# MDL_CONTROL.net
KiCad netlist of a schematic drawn in Altium Designer
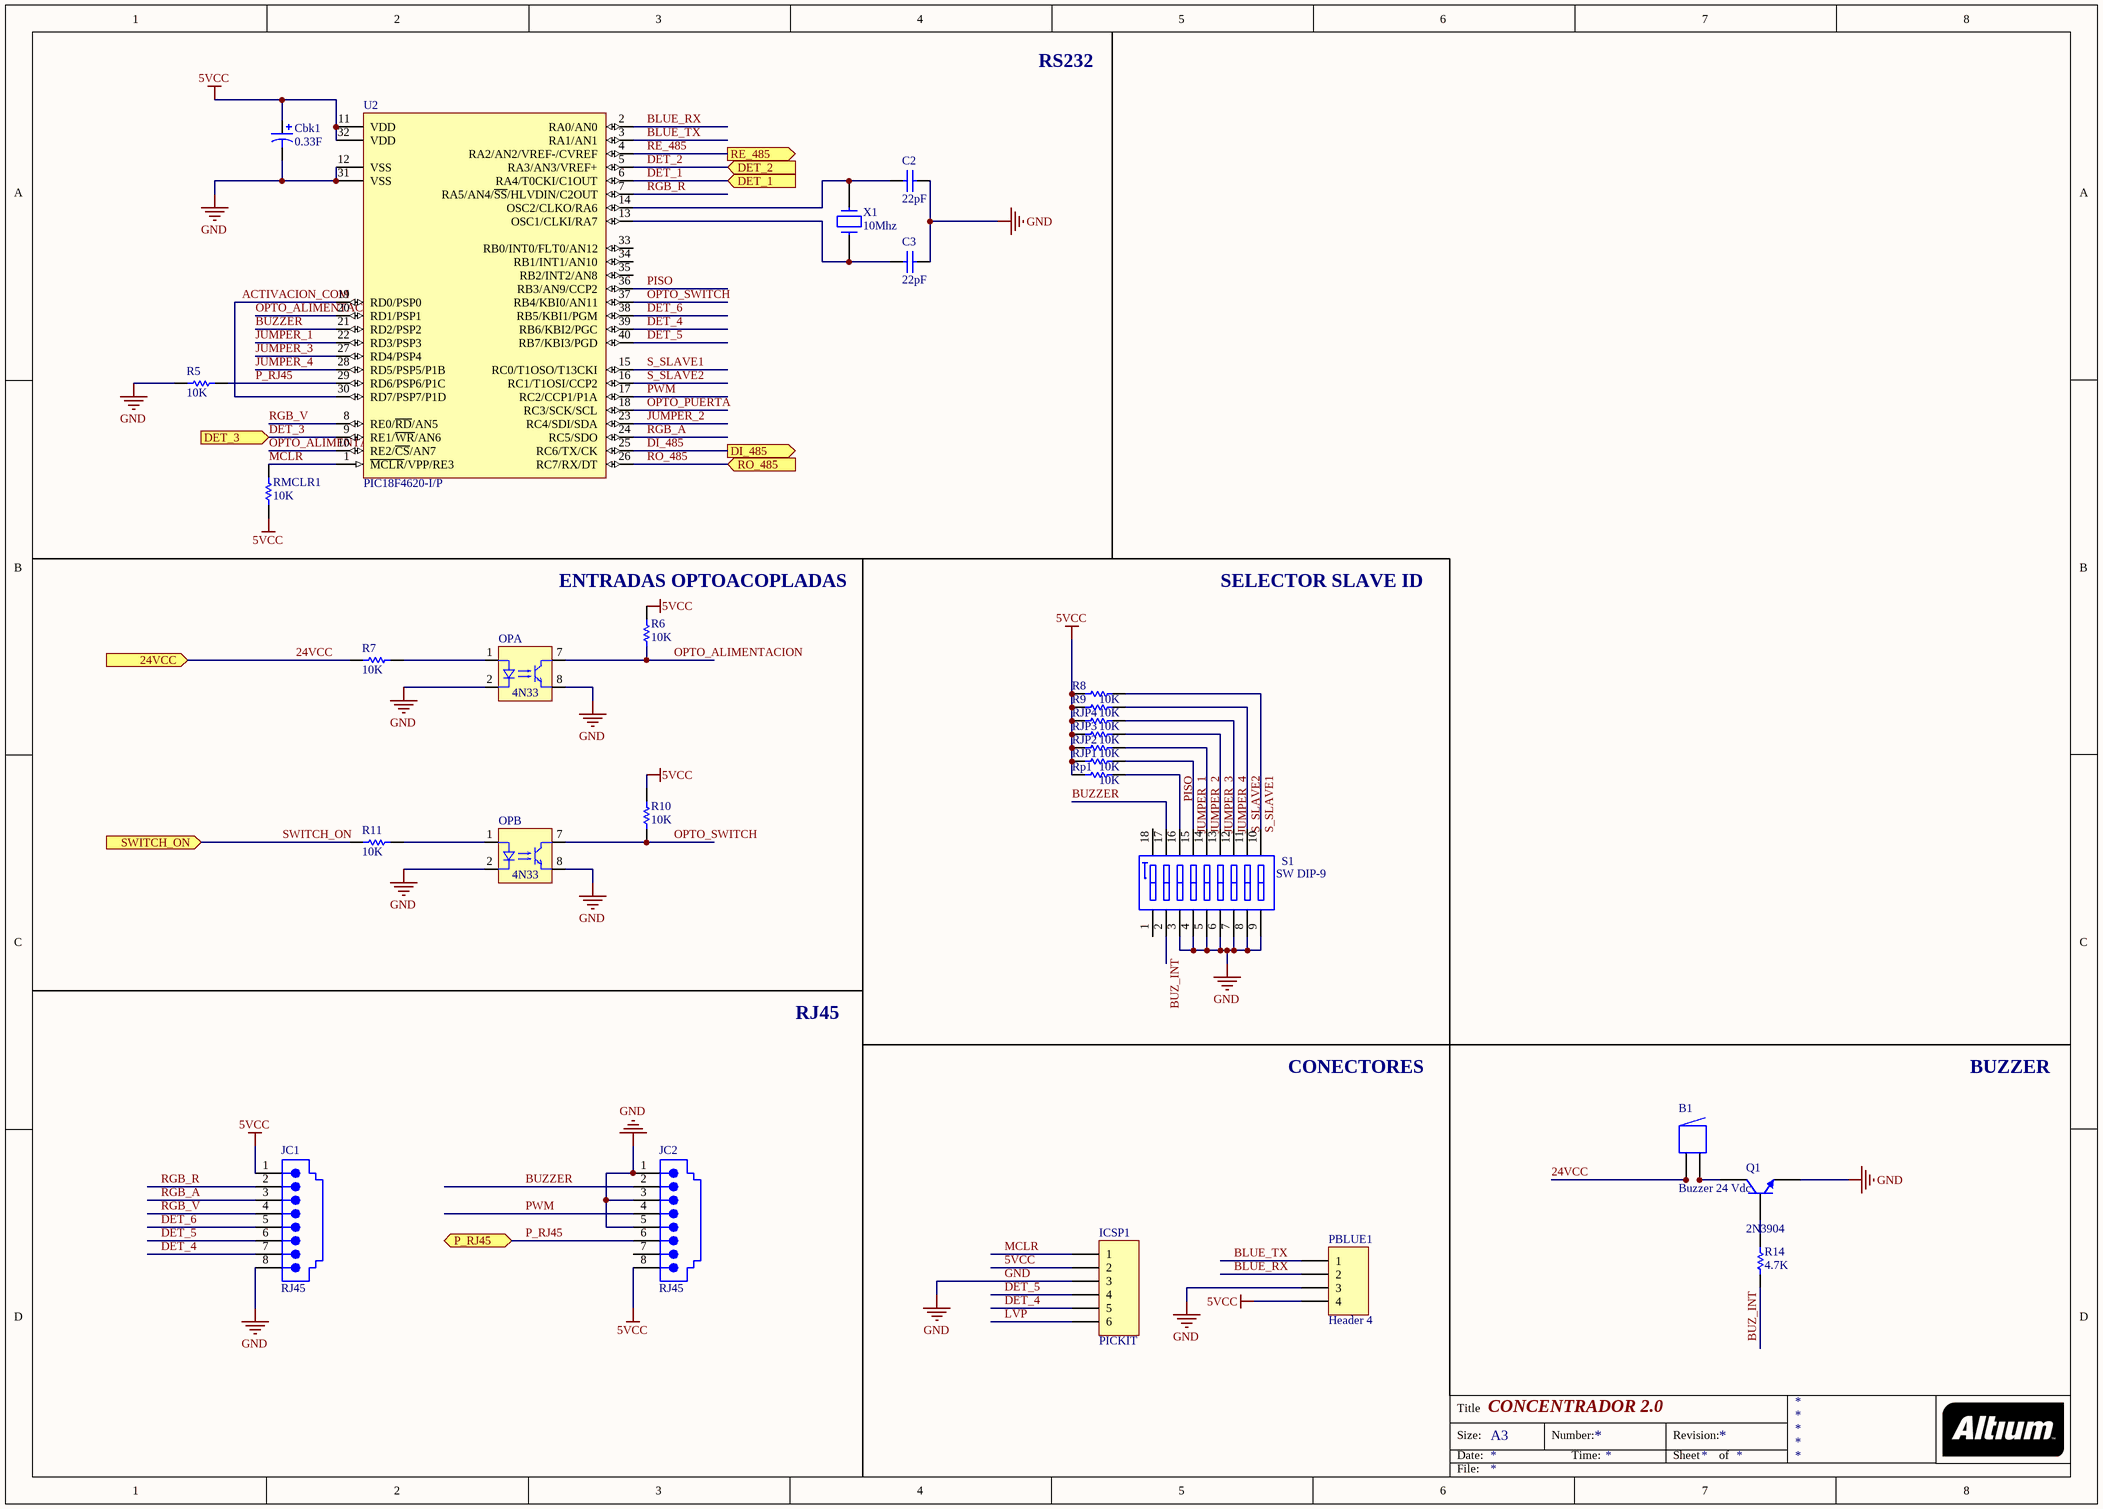
[diagram p0: MDL_CONTROL.SchDoc]

(export (version "E")
  (design (tool "Eeschema 10.0.6"))
  (components
    (comp (ref "B1")
      (value "Buzzer 24 Vdc")
      (footprint "ABSM-1574")
      (description "Magnetic Transducer Buzzer")
      (fields (field (name "PUBLISHER") "Altium Limited"))
      (libsource (lib "Miscellaneous Devices") (part "Buzzer"))
    )
    (comp (ref "C2")
      (value "22pF")
      (footprint "VP31-2.5")
      (description "Dipped Radial Multilayer Ceramic Capacitor COG (NPO): 22pF, 100V")
      (fields (field (name "Comment") "VP31BA220JB") (field (name "PUBLISHER") "Altium Limited"))
      (libsource (lib "Vishay Vitramon Ceramic Dipped Capacitor") (part "VP31BA220JB"))
    )
    (comp (ref "C3")
      (value "22pF")
      (footprint "VP31-2.5")
      (description "Dipped Radial Multilayer Ceramic Capacitor COG (NPO): 22pF, 100V")
      (fields (field (name "Comment") "VP31BA220JB") (field (name "PUBLISHER") "Altium Limited"))
      (libsource (lib "Vishay Vitramon Ceramic Dipped Capacitor") (part "VP31BA220JB"))
    )
    (comp (ref "Cbk1")
      (value "0.33F")
      (footprint "C1000UF")
      (description "Polarized Capacitor (Radial)")
      (fields (field (name "Comment") "Cap Pol1") (field (name "PUBLISHER") "Altium Limited"))
      (libsource (lib "CONTROL BARRAS DE CONTEO") (part "Cap Pol1"))
    )
    (comp (ref "ICSP1")
      (value "PICKIT")
      (footprint "HDR1X6")
      (description "Header, 6-Pin")
      (fields (field (name "PUBLISHER") "Altium Limited"))
      (libsource (lib "CONTROL BARRAS DE CONTEO") (part "Header 6"))
    )
    (comp (ref "JC1")
      (value "RJ45")
      (footprint "15-43-6233")
      (description "Right Angle, Standard Profile, RJ45-Keyed, Flange Mount PCB Jack")
      (fields (field (name "PUBLISHER") "Altium Limited"))
      (libsource (lib "Molex Modular Jack Right Angle") (part "15-43-6233"))
    )
    (comp (ref "JC2")
      (value "RJ45")
      (footprint "15-43-6233")
      (description "Right Angle, Standard Profile, RJ45-Keyed, Flange Mount PCB Jack")
      (fields (field (name "PUBLISHER") "Altium Limited"))
      (libsource (lib "Molex Modular Jack Right Angle") (part "15-43-6233"))
    )
    (comp (ref "OP")
      (value "4N33")
      (footprint "4n35_4n33_6pines")
      (description "Optocoupler, Phototransistor Output, Dual Channel, TTL Compatible, Pb-free")
      (fields (field (name "PUBLISHER") "Altium Limited"))
      (libsource (lib "Vishay Optoelectronic Optocoupler") (part "ILD74"))
    )
    (comp (ref "PBLUE1")
      (value "Header 4")
      (footprint "HDR1X4")
      (description "Header, 4-Pin")
      (fields (field (name "PUBLISHER") "Altium Limited"))
      (libsource (lib "Miscellaneous Connectors") (part "Header 4"))
    )
    (comp (ref "Q1")
      (value "2N3904")
      (footprint "TO-92A")
      (description "NPN General Purpose Amplifier")
      (fields (field (name "PUBLISHER") "Altium Limited"))
      (libsource (lib "Miscellaneous Devices") (part "2N3904"))
    )
    (comp (ref "R5")
      (value "10K")
      (footprint "AXIAL-0.3")
      (description "Resistor")
      (fields (field (name "Comment") "Res") (field (name "PUBLISHER") "Altium Limited"))
      (libsource (lib "Miscellaneous Devices") (part "Res1"))
    )
    (comp (ref "R6")
      (value "10K")
      (footprint "AXIAL-0.3")
      (description "Resistor")
      (fields (field (name "Comment") "Res") (field (name "PUBLISHER") "Altium Limited"))
      (libsource (lib "Miscellaneous Devices") (part "Res1"))
    )
    (comp (ref "R7")
      (value "10K")
      (footprint "AXIAL-0.3")
      (description "Resistor")
      (fields (field (name "Comment") "Res") (field (name "PUBLISHER") "Altium Limited"))
      (libsource (lib "Miscellaneous Devices") (part "Res1"))
    )
    (comp (ref "R8")
      (value "10K")
      (footprint "AXIAL-0.3")
      (description "Resistor")
      (fields (field (name "Comment") "Res") (field (name "PUBLISHER") "Altium Limited"))
      (libsource (lib "Miscellaneous Devices") (part "Res1"))
    )
    (comp (ref "R9")
      (value "10K")
      (footprint "AXIAL-0.3")
      (description "Resistor")
      (fields (field (name "Comment") "Res") (field (name "PUBLISHER") "Altium Limited"))
      (libsource (lib "Miscellaneous Devices") (part "Res1"))
    )
    (comp (ref "R10")
      (value "10K")
      (footprint "AXIAL-0.3")
      (description "Resistor")
      (fields (field (name "Comment") "Res") (field (name "PUBLISHER") "Altium Limited"))
      (libsource (lib "Miscellaneous Devices") (part "Res1"))
    )
    (comp (ref "R11")
      (value "10K")
      (footprint "AXIAL-0.3")
      (description "Resistor")
      (fields (field (name "Comment") "Res") (field (name "PUBLISHER") "Altium Limited"))
      (libsource (lib "Miscellaneous Devices") (part "Res1"))
    )
    (comp (ref "R14")
      (value "4.7K")
      (footprint "AXIAL-0.3")
      (description "Resistor")
      (fields (field (name "Comment") "Res") (field (name "PUBLISHER") "Altium Limited"))
      (libsource (lib "Miscellaneous Devices") (part "Res1"))
    )
    (comp (ref "RJP1")
      (value "10K")
      (footprint "AXIAL-0.3")
      (description "Resistor")
      (fields (field (name "Comment") "Res") (field (name "PUBLISHER") "Altium Limited"))
      (libsource (lib "Miscellaneous Devices") (part "Res1"))
    )
    (comp (ref "RJP2")
      (value "10K")
      (footprint "AXIAL-0.3")
      (description "Resistor")
      (fields (field (name "Comment") "Res") (field (name "PUBLISHER") "Altium Limited"))
      (libsource (lib "Miscellaneous Devices") (part "Res1"))
    )
    (comp (ref "RJP3")
      (value "10K")
      (footprint "AXIAL-0.3")
      (description "Resistor")
      (fields (field (name "Comment") "Res") (field (name "PUBLISHER") "Altium Limited"))
      (libsource (lib "Miscellaneous Devices") (part "Res1"))
    )
    (comp (ref "RJP4")
      (value "10K")
      (footprint "AXIAL-0.3")
      (description "Resistor")
      (fields (field (name "Comment") "Res") (field (name "PUBLISHER") "Altium Limited"))
      (libsource (lib "Miscellaneous Devices") (part "Res1"))
    )
    (comp (ref "RMCLR1")
      (value "10K")
      (footprint "AXIAL-0.3")
      (description "Resistor")
      (fields (field (name "Comment") "Res") (field (name "PUBLISHER") "Altium Limited"))
      (libsource (lib "Miscellaneous Devices") (part "Res1"))
    )
    (comp (ref "Rp1")
      (value "10K")
      (footprint "AXIAL-0.3")
      (description "Resistor")
      (fields (field (name "Comment") "Res") (field (name "PUBLISHER") "Altium Limited"))
      (libsource (lib "Miscellaneous Devices") (part "Res1"))
    )
    (comp (ref "S1")
      (value "SW DIP-9")
      (footprint "DIP-18")
      (description "DIP Switch, 9 Position, SPST")
      (fields (field (name "PUBLISHER") "Altium Limited"))
      (libsource (lib "Miscellaneous Devices") (part "SW DIP-9"))
    )
    (comp (ref "U2")
      (value "PIC18F4620-I/P")
      (footprint "PDIP600-P40")
      (fields (field (name "MANUFACTURER") "Microchip"))
      (libsource (lib "Microchip PIC18") (part "PIC18F4620-I/P"))
    )
    (comp (ref "X1")
      (value "10Mhz")
      (footprint "XTAL-1")
      (description "Cristal de cuarzo")
      (fields (field (name "X1") "10Mhz"))
      (libsource (lib "Cristales de cuarzo") (part "Cristal de cuarzo"))
    )
  )
  (nets
    (net (code "1") (name "/24VCC") (class "Default")
      (node (ref "B1") (pin "1") (pinfunction "1_1") (pintype "passive"))
      (node (ref "B1") (pin "1A") (pinfunction "1A_1A") (pintype "passive"))
      (node (ref "R7") (pin "1") (pinfunction "1_1") (pintype "passive"))
    )
    (net (code "2") (name "/ACTIVACION_COM") (class "Default")
      (node (ref "U2") (pin "19") (pinfunction "RD0/PSP0_19") (pintype "bidirectional"))
      (node (ref "U2") (pin "30") (pinfunction "RD7/PSP7/P1D_30") (pintype "bidirectional"))
    )
    (net (code "3") (name "/BLUE_RX") (class "Default")
      (node (ref "PBLUE1") (pin "2") (pinfunction "2_2") (pintype "passive"))
      (node (ref "U2") (pin "2") (pinfunction "RA0/AN0_2") (pintype "bidirectional"))
    )
    (net (code "4") (name "/BLUE_TX") (class "Default")
      (node (ref "PBLUE1") (pin "1") (pinfunction "1_1") (pintype "passive"))
      (node (ref "U2") (pin "3") (pinfunction "RA1/AN1_3") (pintype "bidirectional"))
    )
    (net (code "5") (name "/BUZZER") (class "Default")
      (node (ref "JC2") (pin "2") (pinfunction "2_2") (pintype "passive"))
      (node (ref "S1") (pin "17") (pinfunction "B2_17") (pintype "passive"))
      (node (ref "U2") (pin "21") (pinfunction "RD2/PSP2_21") (pintype "bidirectional"))
    )
    (net (code "6") (name "/BUZ_INT") (class "Default")
      (node (ref "R14") (pin "1") (pinfunction "1_1") (pintype "passive"))
      (node (ref "S1") (pin "2") (pinfunction "A2_2") (pintype "passive"))
    )
    (net (code "7") (name "/DET_1") (class "Default")
      (node (ref "U2") (pin "6") (pinfunction "RA4/T0CKI/C1OUT_6") (pintype "bidirectional"))
    )
    (net (code "8") (name "/DET_2") (class "Default")
      (node (ref "U2") (pin "5") (pinfunction "RA3/AN3/VREF+_5") (pintype "bidirectional"))
    )
    (net (code "9") (name "/DET_3") (class "Default")
      (node (ref "U2") (pin "9") (pinfunction "RE1/~{WR}/AN6_9") (pintype "bidirectional"))
    )
    (net (code "10") (name "/DET_4") (class "Default")
      (node (ref "ICSP1") (pin "5") (pinfunction "5_5") (pintype "passive"))
      (node (ref "JC1") (pin "7") (pinfunction "7_7") (pintype "passive"))
      (node (ref "U2") (pin "39") (pinfunction "RB6/KBI2/PGC_39") (pintype "bidirectional"))
    )
    (net (code "11") (name "/DET_5") (class "Default")
      (node (ref "ICSP1") (pin "4") (pinfunction "4_4") (pintype "passive"))
      (node (ref "JC1") (pin "6") (pinfunction "6_6") (pintype "passive"))
      (node (ref "U2") (pin "40") (pinfunction "RB7/KBI3/PGD_40") (pintype "bidirectional"))
    )
    (net (code "12") (name "/DET_6") (class "Default")
      (node (ref "JC1") (pin "5") (pinfunction "5_5") (pintype "passive"))
      (node (ref "U2") (pin "38") (pinfunction "RB5/KBI1/PGM_38") (pintype "bidirectional"))
    )
    (net (code "13") (name "/DI_485") (class "Default")
      (node (ref "U2") (pin "25") (pinfunction "RC6/TX/CK_25") (pintype "bidirectional"))
    )
    (net (code "14") (name "/JUMPER_1") (class "Default")
      (node (ref "RJP1") (pin "1") (pinfunction "1_1") (pintype "passive"))
      (node (ref "S1") (pin "15") (pinfunction "B4_15") (pintype "passive"))
      (node (ref "U2") (pin "22") (pinfunction "RD3/PSP3_22") (pintype "bidirectional"))
    )
    (net (code "15") (name "/JUMPER_2") (class "Default")
      (node (ref "RJP2") (pin "1") (pinfunction "1_1") (pintype "passive"))
      (node (ref "S1") (pin "14") (pinfunction "B5_14") (pintype "passive"))
      (node (ref "U2") (pin "23") (pinfunction "RC4/SDI/SDA_23") (pintype "bidirectional"))
    )
    (net (code "16") (name "/JUMPER_3") (class "Default")
      (node (ref "RJP3") (pin "1") (pinfunction "1_1") (pintype "passive"))
      (node (ref "S1") (pin "13") (pinfunction "B6_13") (pintype "passive"))
      (node (ref "U2") (pin "27") (pinfunction "RD4/PSP4_27") (pintype "bidirectional"))
    )
    (net (code "17") (name "/JUMPER_4") (class "Default")
      (node (ref "RJP4") (pin "1") (pinfunction "1_1") (pintype "passive"))
      (node (ref "S1") (pin "12") (pinfunction "B7_12") (pintype "passive"))
      (node (ref "U2") (pin "28") (pinfunction "RD5/PSP5/P1B_28") (pintype "bidirectional"))
    )
    (net (code "18") (name "/LVP") (class "Default")
      (node (ref "ICSP1") (pin "6") (pinfunction "6_6") (pintype "passive"))
    )
    (net (code "19") (name "/MCLR") (class "Default")
      (node (ref "ICSP1") (pin "1") (pinfunction "1_1") (pintype "passive"))
      (node (ref "RMCLR1") (pin "1") (pinfunction "1_1") (pintype "passive"))
      (node (ref "U2") (pin "1") (pinfunction "~{MCLR}/VPP/RE3_1") (pintype "input"))
    )
    (net (code "20") (name "/OPTO_ALIMENTACION") (class "Default")
      (node (ref "OP") (pin "7") (pinfunction "C_7") (pintype "passive"))
      (node (ref "R6") (pin "1") (pinfunction "1_1") (pintype "passive"))
      (node (ref "U2") (pin "10") (pinfunction "RE2/~{CS}/AN7_10") (pintype "bidirectional"))
      (node (ref "U2") (pin "20") (pinfunction "RD1/PSP1_20") (pintype "bidirectional"))
    )
    (net (code "21") (name "/OPTO_PUERTA") (class "Default")
      (node (ref "U2") (pin "18") (pinfunction "RC3/SCK/SCL_18") (pintype "bidirectional"))
    )
    (net (code "22") (name "/OPTO_SWITCH") (class "Default")
      (node (ref "OP") (pin "7") (pinfunction "C_7") (pintype "passive"))
      (node (ref "R10") (pin "1") (pinfunction "1_1") (pintype "passive"))
      (node (ref "U2") (pin "37") (pinfunction "RB4/KBI0/AN11_37") (pintype "bidirectional"))
    )
    (net (code "23") (name "/PISO") (class "Default")
      (node (ref "Rp1") (pin "1") (pinfunction "1_1") (pintype "passive"))
      (node (ref "S1") (pin "16") (pinfunction "B3_16") (pintype "passive"))
      (node (ref "U2") (pin "36") (pinfunction "RB3/AN9/CCP2_36") (pintype "bidirectional"))
    )
    (net (code "24") (name "/PWM") (class "Default")
      (node (ref "JC2") (pin "4") (pinfunction "4_4") (pintype "passive"))
      (node (ref "U2") (pin "17") (pinfunction "RC2/CCP1/P1A_17") (pintype "bidirectional"))
    )
    (net (code "25") (name "/P_RJ45") (class "Default")
      (node (ref "JC2") (pin "6") (pinfunction "6_6") (pintype "passive"))
      (node (ref "R5") (pin "1") (pinfunction "1_1") (pintype "passive"))
      (node (ref "U2") (pin "29") (pinfunction "RD6/PSP6/P1C_29") (pintype "bidirectional"))
    )
    (net (code "26") (name "/RE_485") (class "Default")
      (node (ref "U2") (pin "4") (pinfunction "RA2/AN2/VREF-/CVREF_4") (pintype "bidirectional"))
    )
    (net (code "27") (name "/RGB_A") (class "Default")
      (node (ref "JC1") (pin "3") (pinfunction "3_3") (pintype "passive"))
      (node (ref "U2") (pin "24") (pinfunction "RC5/SDO_24") (pintype "bidirectional"))
    )
    (net (code "28") (name "/RGB_R") (class "Default")
      (node (ref "JC1") (pin "2") (pinfunction "2_2") (pintype "passive"))
      (node (ref "U2") (pin "7") (pinfunction "RA5/AN4/~{SS}/HLVDIN/C2OUT_7") (pintype "bidirectional"))
    )
    (net (code "29") (name "/RGB_V") (class "Default")
      (node (ref "JC1") (pin "4") (pinfunction "4_4") (pintype "passive"))
      (node (ref "U2") (pin "8") (pinfunction "RE0/~{RD}/AN5_8") (pintype "bidirectional"))
    )
    (net (code "30") (name "/RO_485") (class "Default")
      (node (ref "U2") (pin "26") (pinfunction "RC7/RX/DT_26") (pintype "bidirectional"))
    )
    (net (code "31") (name "/SWITCH_ON") (class "Default")
      (node (ref "R11") (pin "1") (pinfunction "1_1") (pintype "passive"))
    )
    (net (code "32") (name "/S_SLAVE1") (class "Default")
      (node (ref "R8") (pin "1") (pinfunction "1_1") (pintype "passive"))
      (node (ref "S1") (pin "10") (pinfunction "B9_10") (pintype "passive"))
      (node (ref "U2") (pin "15") (pinfunction "RC0/T1OSO/T13CKI_15") (pintype "bidirectional"))
    )
    (net (code "33") (name "/S_SLAVE2") (class "Default")
      (node (ref "R9") (pin "1") (pinfunction "1_1") (pintype "passive"))
      (node (ref "S1") (pin "11") (pinfunction "B8_11") (pintype "passive"))
      (node (ref "U2") (pin "16") (pinfunction "RC1/T1OSI/CCP2_16") (pintype "bidirectional"))
    )
    (net (code "34") (name "5VCC") (class "Default")
      (node (ref "Cbk1") (pin "1") (pinfunction "1_1") (pintype "passive"))
      (node (ref "ICSP1") (pin "2") (pinfunction "2_2") (pintype "passive"))
      (node (ref "JC1") (pin "1") (pinfunction "1_1") (pintype "passive"))
      (node (ref "JC2") (pin "8") (pinfunction "8_8") (pintype "passive"))
      (node (ref "PBLUE1") (pin "4") (pinfunction "4_4") (pintype "passive"))
      (node (ref "R10") (pin "2") (pinfunction "2_2") (pintype "passive"))
      (node (ref "R6") (pin "2") (pinfunction "2_2") (pintype "passive"))
      (node (ref "R8") (pin "2") (pinfunction "2_2") (pintype "passive"))
      (node (ref "R9") (pin "2") (pinfunction "2_2") (pintype "passive"))
      (node (ref "RJP1") (pin "2") (pinfunction "2_2") (pintype "passive"))
      (node (ref "RJP2") (pin "2") (pinfunction "2_2") (pintype "passive"))
      (node (ref "RJP3") (pin "2") (pinfunction "2_2") (pintype "passive"))
      (node (ref "RJP4") (pin "2") (pinfunction "2_2") (pintype "passive"))
      (node (ref "RMCLR1") (pin "2") (pinfunction "2_2") (pintype "passive"))
      (node (ref "Rp1") (pin "2") (pinfunction "2_2") (pintype "passive"))
      (node (ref "U2") (pin "11") (pinfunction "VDD_11") (pintype "power_in"))
      (node (ref "U2") (pin "32") (pinfunction "VDD_32") (pintype "power_in"))
    )
    (net (code "35") (name "GND") (class "Default")
      (node (ref "C2") (pin "2") (pinfunction "2_2") (pintype "passive"))
      (node (ref "C3") (pin "1") (pinfunction "1_1") (pintype "passive"))
      (node (ref "Cbk1") (pin "2") (pinfunction "2_2") (pintype "passive"))
      (node (ref "ICSP1") (pin "3") (pinfunction "3_3") (pintype "passive"))
      (node (ref "JC1") (pin "8") (pinfunction "8_8") (pintype "passive"))
      (node (ref "JC2") (pin "1") (pinfunction "1_1") (pintype "passive"))
      (node (ref "JC2") (pin "3") (pinfunction "3_3") (pintype "passive"))
      (node (ref "JC2") (pin "5") (pinfunction "5_5") (pintype "passive"))
      (node (ref "OP") (pin "2") (pinfunction "K_2") (pintype "passive"))
      (node (ref "OP") (pin "8") (pinfunction "E_8") (pintype "passive"))
      (node (ref "PBLUE1") (pin "3") (pinfunction "3_3") (pintype "passive"))
      (node (ref "Q1") (pin "1") (pinfunction "E_1") (pintype "passive"))
      (node (ref "R5") (pin "2") (pinfunction "2_2") (pintype "passive"))
      (node (ref "S1") (pin "3") (pinfunction "A3_3") (pintype "passive"))
      (node (ref "S1") (pin "4") (pinfunction "A4_4") (pintype "passive"))
      (node (ref "S1") (pin "5") (pinfunction "A5_5") (pintype "passive"))
      (node (ref "S1") (pin "6") (pinfunction "A6_6") (pintype "passive"))
      (node (ref "S1") (pin "7") (pinfunction "A7_7") (pintype "passive"))
      (node (ref "S1") (pin "8") (pinfunction "A8_8") (pintype "passive"))
      (node (ref "S1") (pin "9") (pinfunction "A9_9") (pintype "passive"))
      (node (ref "U2") (pin "12") (pinfunction "VSS_12") (pintype "power_in"))
      (node (ref "U2") (pin "31") (pinfunction "VSS_31") (pintype "power_in"))
    )
    (net (code "36") (name "Net-(OPA-A)") (class "Default")
      (node (ref "OP") (pin "1") (pinfunction "A_1") (pintype "passive"))
      (node (ref "R7") (pin "2") (pinfunction "2_2") (pintype "passive"))
    )
    (net (code "37") (name "Net-(OPB-A)") (class "Default")
      (node (ref "OP") (pin "1") (pinfunction "A_1") (pintype "passive"))
      (node (ref "R11") (pin "2") (pinfunction "2_2") (pintype "passive"))
    )
    (net (code "38") (name "Net-(Q1-B)") (class "Default")
      (node (ref "Q1") (pin "2") (pinfunction "B_2") (pintype "passive"))
      (node (ref "R14") (pin "2") (pinfunction "2_2") (pintype "passive"))
    )
    (net (code "39") (name "Net-(Q1-C)") (class "Default")
      (node (ref "B1") (pin "2") (pinfunction "2_2") (pintype "passive"))
      (node (ref "B1") (pin "2A") (pinfunction "2A_2A") (pintype "passive"))
      (node (ref "Q1") (pin "3") (pinfunction "C_3") (pintype "passive"))
    )
    (net (code "40") (name "Net-(U2-OSC1{slash}CLKI{slash}RA7)") (class "Default")
      (node (ref "C3") (pin "2") (pinfunction "2_2") (pintype "passive"))
      (node (ref "U2") (pin "13") (pinfunction "OSC1/CLKI/RA7_13") (pintype "bidirectional"))
      (node (ref "X1") (pin "2") (pinfunction "2_2") (pintype "passive"))
    )
    (net (code "41") (name "Net-(U2-OSC2{slash}CLKO{slash}RA6)") (class "Default")
      (node (ref "C2") (pin "1") (pinfunction "1_1") (pintype "passive"))
      (node (ref "U2") (pin "14") (pinfunction "OSC2/CLKO/RA6_14") (pintype "bidirectional"))
      (node (ref "X1") (pin "1") (pinfunction "1_1") (pintype "passive"))
    )
    (net (code "42") (name "unconnected-(JC2-Pad7)") (class "Default")
      (node (ref "JC2") (pin "7") (pinfunction "7_7") (pintype "passive"))
    )
    (net (code "43") (name "unconnected-(S1-A1-Pad1)") (class "Default")
      (node (ref "S1") (pin "1") (pinfunction "A1_1") (pintype "passive"))
    )
    (net (code "44") (name "unconnected-(S1-B1-Pad18)") (class "Default")
      (node (ref "S1") (pin "18") (pinfunction "B1_18") (pintype "passive"))
    )
    (net (code "45") (name "unconnected-(U2-RB0{slash}INT0{slash}FLT0{slash}AN12-Pad33)") (class "Default")
      (node (ref "U2") (pin "33") (pinfunction "RB0/INT0/FLT0/AN12_33") (pintype "bidirectional"))
    )
    (net (code "46") (name "unconnected-(U2-RB1{slash}INT1{slash}AN10-Pad34)") (class "Default")
      (node (ref "U2") (pin "34") (pinfunction "RB1/INT1/AN10_34") (pintype "bidirectional"))
    )
    (net (code "47") (name "unconnected-(U2-RB2{slash}INT2{slash}AN8-Pad35)") (class "Default")
      (node (ref "U2") (pin "35") (pinfunction "RB2/INT2/AN8_35") (pintype "bidirectional"))
    )
  )
)
